# LDO.net
KiCad netlist of a schematic drawn in Altium Designer
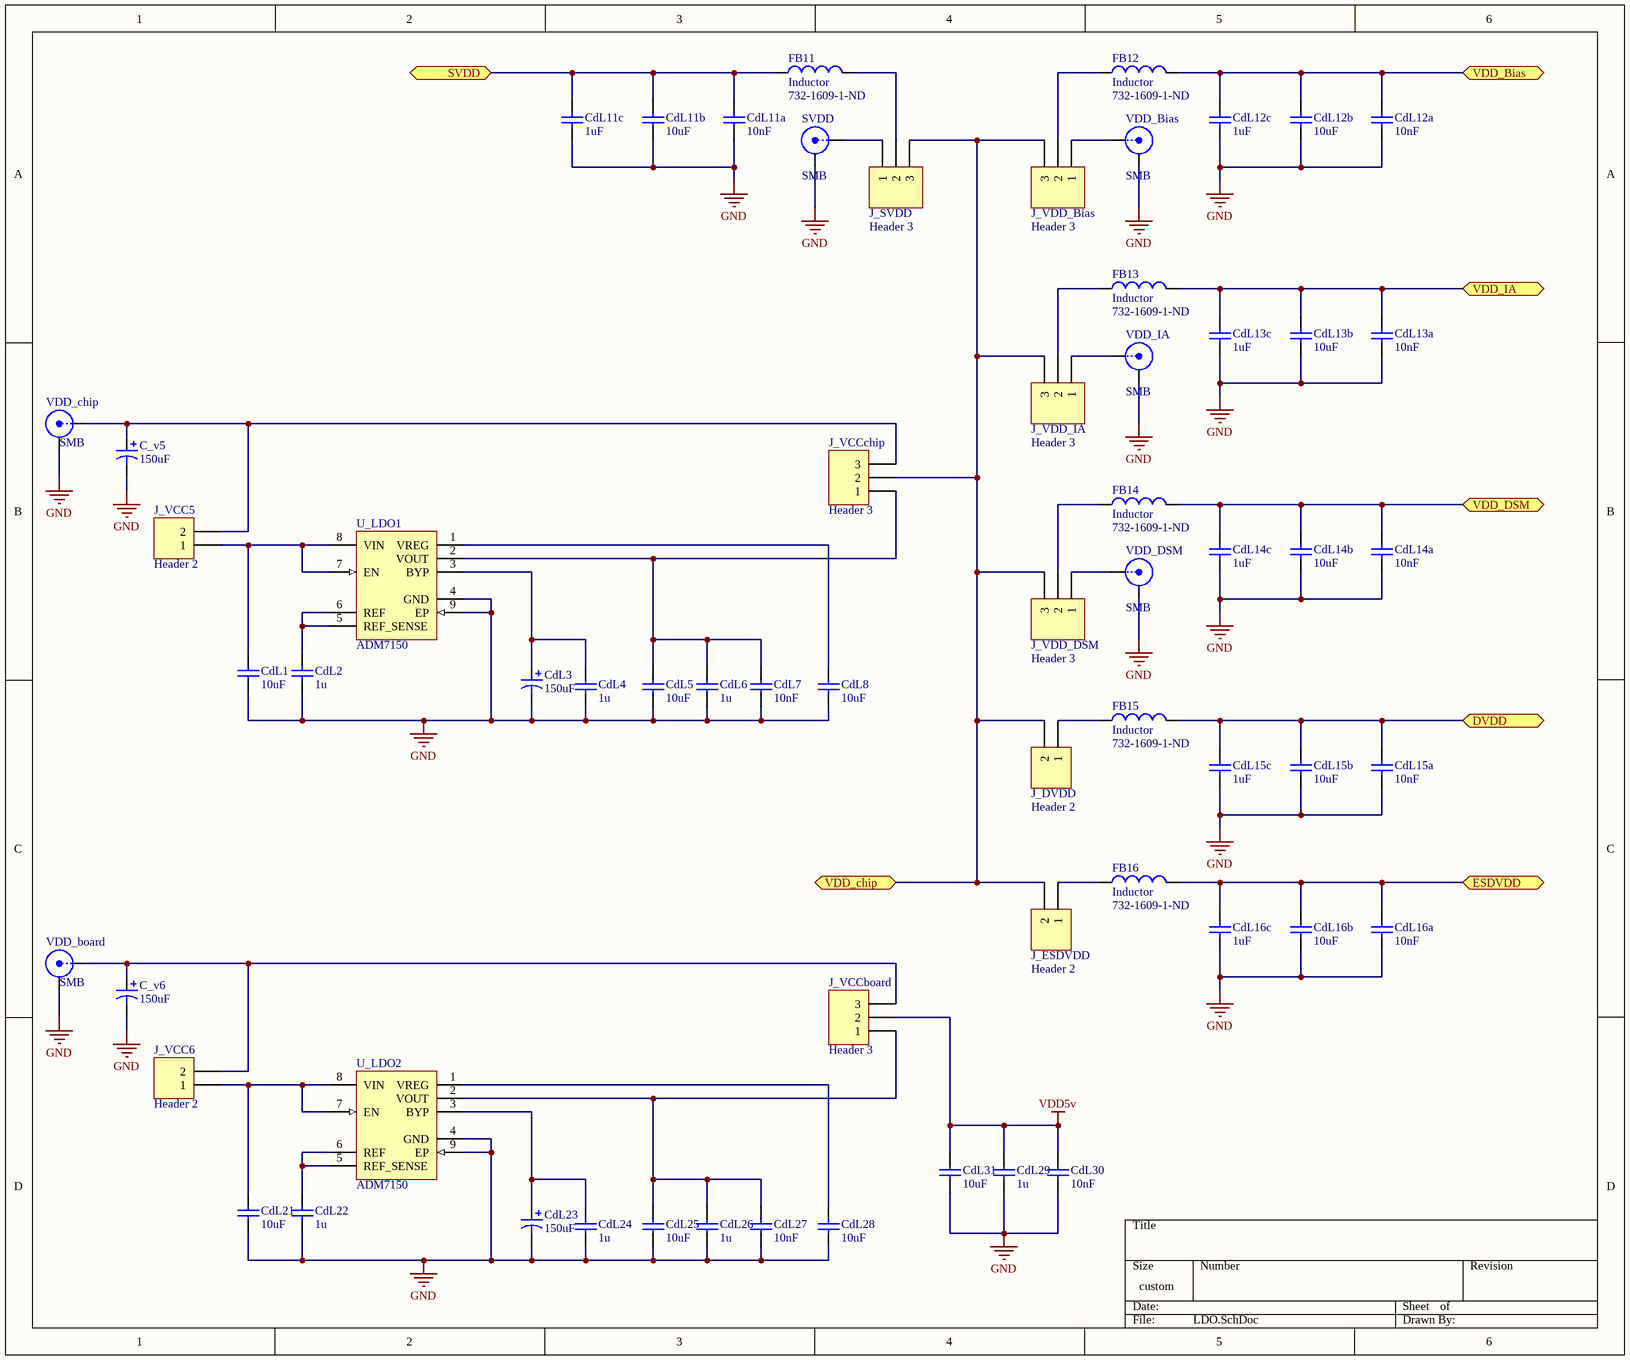
[diagram p0: LDO.SchDoc]

(export (version "E")
  (design (tool "Eeschema 10.0.6"))
  (components
    (comp (ref "CdL1")
      (value "10uF")
      (footprint "6-0805_M")
      (description "Capacitor")
      (fields (field (name "Comment") "Cap") (field (name "PUBLISHER") "Altium Limited"))
      (libsource (lib "Miscellaneous Devices") (part "Cap"))
    )
    (comp (ref "CdL2")
      (value "1u")
      (footprint "6-0805_M")
      (description "Capacitor")
      (fields (field (name "Comment") "Cap") (field (name "PUBLISHER") "Altium Limited"))
      (libsource (lib "Miscellaneous Devices") (part "Cap"))
    )
    (comp (ref "CdL3")
      (value "150uF")
      (footprint "C1210_M")
      (description "Polarized Capacitor (Radial)")
      (fields (field (name "Comment") "Cap Pol1") (field (name "PUBLISHER") "Altium Limited"))
      (libsource (lib "Miscellaneous Devices") (part "Cap Pol1"))
    )
    (comp (ref "CdL4")
      (value "1u")
      (footprint "6-0805_M")
      (description "Capacitor")
      (fields (field (name "Comment") "Cap") (field (name "PUBLISHER") "Altium Limited"))
      (libsource (lib "Miscellaneous Devices") (part "Cap"))
    )
    (comp (ref "CdL5")
      (value "10uF")
      (footprint "6-0805_M")
      (description "Capacitor")
      (fields (field (name "Comment") "Cap") (field (name "PUBLISHER") "Altium Limited"))
      (libsource (lib "Miscellaneous Devices") (part "Cap"))
    )
    (comp (ref "CdL6")
      (value "1u")
      (footprint "6-0805_M")
      (description "Capacitor")
      (fields (field (name "Comment") "Cap") (field (name "PUBLISHER") "Altium Limited"))
      (libsource (lib "Miscellaneous Devices") (part "Cap"))
    )
    (comp (ref "CdL7")
      (value "10nF")
      (footprint "6-0805_M")
      (description "Capacitor")
      (fields (field (name "Comment") "Cap") (field (name "PUBLISHER") "Altium Limited"))
      (libsource (lib "Miscellaneous Devices") (part "Cap"))
    )
    (comp (ref "CdL8")
      (value "10uF")
      (footprint "6-0805_M")
      (description "Capacitor")
      (fields (field (name "Comment") "Cap") (field (name "PUBLISHER") "Altium Limited"))
      (libsource (lib "Miscellaneous Devices") (part "Cap"))
    )
    (comp (ref "CdL11a")
      (value "10nF")
      (footprint "1608[0603]")
      (description "Capacitor")
      (fields (field (name "Comment") "Cap") (field (name "PUBLISHER") "Altium Limited"))
      (libsource (lib "Miscellaneous Devices") (part "Cap"))
    )
    (comp (ref "CdL11b")
      (value "10uF")
      (footprint "1608[0603]")
      (description "Capacitor")
      (fields (field (name "Comment") "Cap") (field (name "PUBLISHER") "Altium Limited"))
      (libsource (lib "Miscellaneous Devices") (part "Cap"))
    )
    (comp (ref "CdL11c")
      (value "1uF")
      (footprint "1608[0603]")
      (description "Capacitor")
      (fields (field (name "Comment") "Cap") (field (name "PUBLISHER") "Altium Limited"))
      (libsource (lib "Miscellaneous Devices") (part "Cap"))
    )
    (comp (ref "CdL12a")
      (value "10nF")
      (footprint "1608[0603]")
      (description "Capacitor")
      (fields (field (name "Comment") "Cap") (field (name "PUBLISHER") "Altium Limited"))
      (libsource (lib "Miscellaneous Devices") (part "Cap"))
    )
    (comp (ref "CdL12b")
      (value "10uF")
      (footprint "1608[0603]")
      (description "Capacitor")
      (fields (field (name "Comment") "Cap") (field (name "PUBLISHER") "Altium Limited"))
      (libsource (lib "Miscellaneous Devices") (part "Cap"))
    )
    (comp (ref "CdL12c")
      (value "1uF")
      (footprint "1608[0603]")
      (description "Capacitor")
      (fields (field (name "Comment") "Cap") (field (name "PUBLISHER") "Altium Limited"))
      (libsource (lib "Miscellaneous Devices") (part "Cap"))
    )
    (comp (ref "CdL13a")
      (value "10nF")
      (footprint "1608[0603]")
      (description "Capacitor")
      (fields (field (name "Comment") "Cap") (field (name "PUBLISHER") "Altium Limited"))
      (libsource (lib "Miscellaneous Devices") (part "Cap"))
    )
    (comp (ref "CdL13b")
      (value "10uF")
      (footprint "1608[0603]")
      (description "Capacitor")
      (fields (field (name "Comment") "Cap") (field (name "PUBLISHER") "Altium Limited"))
      (libsource (lib "Miscellaneous Devices") (part "Cap"))
    )
    (comp (ref "CdL13c")
      (value "1uF")
      (footprint "1608[0603]")
      (description "Capacitor")
      (fields (field (name "Comment") "Cap") (field (name "PUBLISHER") "Altium Limited"))
      (libsource (lib "Miscellaneous Devices") (part "Cap"))
    )
    (comp (ref "CdL14a")
      (value "10nF")
      (footprint "1608[0603]")
      (description "Capacitor")
      (fields (field (name "Comment") "Cap") (field (name "PUBLISHER") "Altium Limited"))
      (libsource (lib "Miscellaneous Devices") (part "Cap"))
    )
    (comp (ref "CdL14b")
      (value "10uF")
      (footprint "1608[0603]")
      (description "Capacitor")
      (fields (field (name "Comment") "Cap") (field (name "PUBLISHER") "Altium Limited"))
      (libsource (lib "Miscellaneous Devices") (part "Cap"))
    )
    (comp (ref "CdL14c")
      (value "1uF")
      (footprint "1608[0603]")
      (description "Capacitor")
      (fields (field (name "Comment") "Cap") (field (name "PUBLISHER") "Altium Limited"))
      (libsource (lib "Miscellaneous Devices") (part "Cap"))
    )
    (comp (ref "CdL15a")
      (value "10nF")
      (footprint "1608[0603]")
      (description "Capacitor")
      (fields (field (name "Comment") "Cap") (field (name "PUBLISHER") "Altium Limited"))
      (libsource (lib "Miscellaneous Devices") (part "Cap"))
    )
    (comp (ref "CdL15b")
      (value "10uF")
      (footprint "1608[0603]")
      (description "Capacitor")
      (fields (field (name "Comment") "Cap") (field (name "PUBLISHER") "Altium Limited"))
      (libsource (lib "Miscellaneous Devices") (part "Cap"))
    )
    (comp (ref "CdL15c")
      (value "1uF")
      (footprint "1608[0603]")
      (description "Capacitor")
      (fields (field (name "Comment") "Cap") (field (name "PUBLISHER") "Altium Limited"))
      (libsource (lib "Miscellaneous Devices") (part "Cap"))
    )
    (comp (ref "CdL16a")
      (value "10nF")
      (footprint "1608[0603]")
      (description "Capacitor")
      (fields (field (name "Comment") "Cap") (field (name "PUBLISHER") "Altium Limited"))
      (libsource (lib "Miscellaneous Devices") (part "Cap"))
    )
    (comp (ref "CdL16b")
      (value "10uF")
      (footprint "1608[0603]")
      (description "Capacitor")
      (fields (field (name "Comment") "Cap") (field (name "PUBLISHER") "Altium Limited"))
      (libsource (lib "Miscellaneous Devices") (part "Cap"))
    )
    (comp (ref "CdL16c")
      (value "1uF")
      (footprint "1608[0603]")
      (description "Capacitor")
      (fields (field (name "Comment") "Cap") (field (name "PUBLISHER") "Altium Limited"))
      (libsource (lib "Miscellaneous Devices") (part "Cap"))
    )
    (comp (ref "CdL21")
      (value "10uF")
      (footprint "6-0805_M")
      (description "Capacitor")
      (fields (field (name "Comment") "Cap") (field (name "PUBLISHER") "Altium Limited"))
      (libsource (lib "Miscellaneous Devices") (part "Cap"))
    )
    (comp (ref "CdL22")
      (value "1u")
      (footprint "6-0805_M")
      (description "Capacitor")
      (fields (field (name "Comment") "Cap") (field (name "PUBLISHER") "Altium Limited"))
      (libsource (lib "Miscellaneous Devices") (part "Cap"))
    )
    (comp (ref "CdL23")
      (value "150uF")
      (footprint "C1210_M")
      (description "Polarized Capacitor (Radial)")
      (fields (field (name "Comment") "Cap Pol1") (field (name "PUBLISHER") "Altium Limited"))
      (libsource (lib "Miscellaneous Devices") (part "Cap Pol1"))
    )
    (comp (ref "CdL24")
      (value "1u")
      (footprint "6-0805_M")
      (description "Capacitor")
      (fields (field (name "Comment") "Cap") (field (name "PUBLISHER") "Altium Limited"))
      (libsource (lib "Miscellaneous Devices") (part "Cap"))
    )
    (comp (ref "CdL25")
      (value "10uF")
      (footprint "6-0805_M")
      (description "Capacitor")
      (fields (field (name "Comment") "Cap") (field (name "PUBLISHER") "Altium Limited"))
      (libsource (lib "Miscellaneous Devices") (part "Cap"))
    )
    (comp (ref "CdL26")
      (value "1u")
      (footprint "6-0805_M")
      (description "Capacitor")
      (fields (field (name "Comment") "Cap") (field (name "PUBLISHER") "Altium Limited"))
      (libsource (lib "Miscellaneous Devices") (part "Cap"))
    )
    (comp (ref "CdL27")
      (value "10nF")
      (footprint "6-0805_M")
      (description "Capacitor")
      (fields (field (name "Comment") "Cap") (field (name "PUBLISHER") "Altium Limited"))
      (libsource (lib "Miscellaneous Devices") (part "Cap"))
    )
    (comp (ref "CdL28")
      (value "10uF")
      (footprint "6-0805_M")
      (description "Capacitor")
      (fields (field (name "Comment") "Cap") (field (name "PUBLISHER") "Altium Limited"))
      (libsource (lib "Miscellaneous Devices") (part "Cap"))
    )
    (comp (ref "CdL29")
      (value "1u")
      (footprint "6-0805_M")
      (description "Capacitor")
      (fields (field (name "Comment") "Cap") (field (name "PUBLISHER") "Altium Limited"))
      (libsource (lib "Miscellaneous Devices") (part "Cap"))
    )
    (comp (ref "CdL30")
      (value "10nF")
      (footprint "6-0805_M")
      (description "Capacitor")
      (fields (field (name "Comment") "Cap") (field (name "PUBLISHER") "Altium Limited"))
      (libsource (lib "Miscellaneous Devices") (part "Cap"))
    )
    (comp (ref "CdL31")
      (value "10uF")
      (footprint "6-0805_M")
      (description "Capacitor")
      (fields (field (name "Comment") "Cap") (field (name "PUBLISHER") "Altium Limited"))
      (libsource (lib "Miscellaneous Devices") (part "Cap"))
    )
    (comp (ref "C_v5")
      (value "150uF")
      (footprint "C1210_M")
      (description "Polarized Capacitor (Radial)")
      (fields (field (name "Comment") "Cap Pol1") (field (name "PUBLISHER") "Altium Limited"))
      (libsource (lib "Miscellaneous Devices") (part "Cap Pol1"))
    )
    (comp (ref "C_v6")
      (value "150uF")
      (footprint "C1210_M")
      (description "Polarized Capacitor (Radial)")
      (fields (field (name "Comment") "Cap Pol1") (field (name "PUBLISHER") "Altium Limited"))
      (libsource (lib "Miscellaneous Devices") (part "Cap Pol1"))
    )
    (comp (ref "FB11")
      (value "Inductor")
      (footprint "C0805")
      (fields
        (field (name "SUPPLIER PART NUMBER 1") "732-1609-1-ND")
        (field (name "MANUFACTURER") "Wurth Electronics Inc")
        (field (name "MANUFACTURER PART NUMBER") "742792093")
        (field (name "PUBLISHER") "Altium Limited")
      )
      (libsource (lib "") (part "Inductor_1"))
    )
    (comp (ref "FB12")
      (value "Inductor")
      (footprint "C0805")
      (fields
        (field (name "SUPPLIER PART NUMBER 1") "732-1609-1-ND")
        (field (name "MANUFACTURER") "Wurth Electronics Inc")
        (field (name "MANUFACTURER PART NUMBER") "742792093")
        (field (name "PUBLISHER") "Altium Limited")
      )
      (libsource (lib "Miscellaneous Devices") (part "Inductor"))
    )
    (comp (ref "FB13")
      (value "Inductor")
      (footprint "C0805")
      (fields
        (field (name "SUPPLIER PART NUMBER 1") "732-1609-1-ND")
        (field (name "MANUFACTURER") "Wurth Electronics Inc")
        (field (name "MANUFACTURER PART NUMBER") "742792093")
        (field (name "PUBLISHER") "Altium Limited")
      )
      (libsource (lib "Miscellaneous Devices") (part "Inductor"))
    )
    (comp (ref "FB14")
      (value "Inductor")
      (footprint "C0805")
      (fields
        (field (name "SUPPLIER PART NUMBER 1") "732-1609-1-ND")
        (field (name "MANUFACTURER") "Wurth Electronics Inc")
        (field (name "MANUFACTURER PART NUMBER") "742792093")
        (field (name "PUBLISHER") "Altium Limited")
      )
      (libsource (lib "Miscellaneous Devices") (part "Inductor"))
    )
    (comp (ref "FB15")
      (value "Inductor")
      (footprint "C0805")
      (fields
        (field (name "SUPPLIER PART NUMBER 1") "732-1609-1-ND")
        (field (name "MANUFACTURER") "Wurth Electronics Inc")
        (field (name "MANUFACTURER PART NUMBER") "742792093")
        (field (name "PUBLISHER") "Altium Limited")
      )
      (libsource (lib "Miscellaneous Devices") (part "Inductor"))
    )
    (comp (ref "FB16")
      (value "Inductor")
      (footprint "C0805")
      (fields
        (field (name "SUPPLIER PART NUMBER 1") "732-1609-1-ND")
        (field (name "MANUFACTURER") "Wurth Electronics Inc")
        (field (name "MANUFACTURER PART NUMBER") "742792093")
        (field (name "PUBLISHER") "Altium Limited")
      )
      (libsource (lib "Miscellaneous Devices") (part "Inductor"))
    )
    (comp (ref "J_DVDD")
      (value "Header 2")
      (footprint "HDR1X2")
      (description "Header, 2-Pin")
      (fields (field (name "PUBLISHER") "Altium Limited"))
      (libsource (lib "") (part "Header 2_1"))
    )
    (comp (ref "J_ESDVDD")
      (value "Header 2")
      (footprint "HDR1X2")
      (description "Header, 2-Pin")
      (fields (field (name "PUBLISHER") "Altium Limited"))
      (libsource (lib "") (part "Header 2_1"))
    )
    (comp (ref "J_SVDD")
      (value "Header 3")
      (footprint "HDR1X3")
      (description "Header, 3-Pin")
      (fields (field (name "PUBLISHER") "Altium Limited"))
      (libsource (lib "Miscellaneous Connectors") (part "Header 3"))
    )
    (comp (ref "J_VCC5")
      (value "Header 2")
      (footprint "HDR1X2")
      (description "Header, 2-Pin")
      (fields (field (name "PUBLISHER") "Altium Limited"))
      (libsource (lib "Miscellaneous Connectors") (part "Header 2"))
    )
    (comp (ref "J_VCC6")
      (value "Header 2")
      (footprint "HDR1X2")
      (description "Header, 2-Pin")
      (fields (field (name "PUBLISHER") "Altium Limited"))
      (libsource (lib "Miscellaneous Connectors") (part "Header 2"))
    )
    (comp (ref "J_VCCboard")
      (value "Header 3")
      (footprint "HDR1X3")
      (description "Header, 3-Pin")
      (fields (field (name "PUBLISHER") "Altium Limited"))
      (libsource (lib "Miscellaneous Connectors") (part "Header 3"))
    )
    (comp (ref "J_VCCchip")
      (value "Header 3")
      (footprint "HDR1X3")
      (description "Header, 3-Pin")
      (fields (field (name "PUBLISHER") "Altium Limited"))
      (libsource (lib "Miscellaneous Connectors") (part "Header 3"))
    )
    (comp (ref "J_VDD_Bias")
      (value "Header 3")
      (footprint "HDR1X3")
      (description "Header, 3-Pin")
      (fields (field (name "PUBLISHER") "Altium Limited"))
      (libsource (lib "") (part "Header 3_1"))
    )
    (comp (ref "J_VDD_DSM")
      (value "Header 3")
      (footprint "HDR1X3")
      (description "Header, 3-Pin")
      (fields (field (name "PUBLISHER") "Altium Limited"))
      (libsource (lib "") (part "Header 3_1"))
    )
    (comp (ref "J_VDD_IA")
      (value "Header 3")
      (footprint "HDR1X3")
      (description "Header, 3-Pin")
      (fields (field (name "PUBLISHER") "Altium Limited"))
      (libsource (lib "") (part "Header 3_1"))
    )
    (comp (ref "SVDD")
      (value "SMB")
      (footprint "SMB_V-RJ45")
      (description "SMB Straight Connector")
      (fields (field (name "PUBLISHER") "Altium Limited"))
      (libsource (lib "Miscellaneous Connectors") (part "SMB"))
    )
    (comp (ref "U_LDO1")
      (value "ADM7150")
      (footprint "ADM7150")
      (description "800 mA Ultralow Noise, High PSRR, RF Linear Regulator")
      (fields (field (name "MANUFACTURER") "Analog Devices") (field (name "PARTNUMBER") "ADP1707ARDZ-3.3-R7"))
      (libsource (lib "custom") (part "ADM7150"))
    )
    (comp (ref "U_LDO2")
      (value "ADM7150")
      (footprint "ADM7150")
      (description "800 mA Ultralow Noise, High PSRR, RF Linear Regulator")
      (fields (field (name "MANUFACTURER") "Analog Devices") (field (name "PARTNUMBER") "ADP1707ARDZ-3.3-R7"))
      (libsource (lib "custom") (part "ADM7150"))
    )
    (comp (ref "VDD_Bias")
      (value "SMB")
      (footprint "SMB_V-RJ45")
      (description "SMB Straight Connector")
      (fields (field (name "PUBLISHER") "Altium Limited"))
      (libsource (lib "Miscellaneous Connectors") (part "SMB"))
    )
    (comp (ref "VDD_board")
      (value "SMB")
      (footprint "SMB_V-RJ45")
      (description "SMB Straight Connector")
      (fields (field (name "PUBLISHER") "Altium Limited"))
      (libsource (lib "Miscellaneous Connectors") (part "SMB"))
    )
    (comp (ref "VDD_chip")
      (value "SMB")
      (footprint "SMB_V-RJ45")
      (description "SMB Straight Connector")
      (fields (field (name "PUBLISHER") "Altium Limited"))
      (libsource (lib "Miscellaneous Connectors") (part "SMB"))
    )
    (comp (ref "VDD_DSM")
      (value "SMB")
      (footprint "SMB_V-RJ45")
      (description "SMB Straight Connector")
      (fields (field (name "PUBLISHER") "Altium Limited"))
      (libsource (lib "Miscellaneous Connectors") (part "SMB"))
    )
    (comp (ref "VDD_IA")
      (value "SMB")
      (footprint "SMB_V-RJ45")
      (description "SMB Straight Connector")
      (fields (field (name "PUBLISHER") "Altium Limited"))
      (libsource (lib "Miscellaneous Connectors") (part "SMB"))
    )
  )
  (nets
    (net (code "1") (name "/DVDD") (class "Default")
      (node (ref "CdL15a") (pin "1") (pinfunction "1_1") (pintype "passive"))
      (node (ref "CdL15b") (pin "1") (pinfunction "1_1") (pintype "passive"))
      (node (ref "CdL15c") (pin "1") (pinfunction "1_1") (pintype "passive"))
      (node (ref "FB15") (pin "2") (pinfunction "2_2") (pintype "passive"))
    )
    (net (code "2") (name "/ESDVDD") (class "Default")
      (node (ref "CdL16a") (pin "1") (pinfunction "1_1") (pintype "passive"))
      (node (ref "CdL16b") (pin "1") (pinfunction "1_1") (pintype "passive"))
      (node (ref "CdL16c") (pin "1") (pinfunction "1_1") (pintype "passive"))
      (node (ref "FB16") (pin "2") (pinfunction "2_2") (pintype "passive"))
    )
    (net (code "3") (name "/SVDD") (class "Default")
      (node (ref "CdL11a") (pin "1") (pinfunction "1_1") (pintype "passive"))
      (node (ref "CdL11b") (pin "1") (pinfunction "1_1") (pintype "passive"))
      (node (ref "CdL11c") (pin "1") (pinfunction "1_1") (pintype "passive"))
      (node (ref "FB11") (pin "2") (pinfunction "2_2") (pintype "passive"))
    )
    (net (code "4") (name "/VDD_Bias") (class "Default")
      (node (ref "CdL12a") (pin "1") (pinfunction "1_1") (pintype "passive"))
      (node (ref "CdL12b") (pin "1") (pinfunction "1_1") (pintype "passive"))
      (node (ref "CdL12c") (pin "1") (pinfunction "1_1") (pintype "passive"))
      (node (ref "FB12") (pin "2") (pinfunction "2_2") (pintype "passive"))
    )
    (net (code "5") (name "/VDD_DSM") (class "Default")
      (node (ref "CdL14a") (pin "1") (pinfunction "1_1") (pintype "passive"))
      (node (ref "CdL14b") (pin "1") (pinfunction "1_1") (pintype "passive"))
      (node (ref "CdL14c") (pin "1") (pinfunction "1_1") (pintype "passive"))
      (node (ref "FB14") (pin "2") (pinfunction "2_2") (pintype "passive"))
    )
    (net (code "6") (name "/VDD_IA") (class "Default")
      (node (ref "CdL13a") (pin "1") (pinfunction "1_1") (pintype "passive"))
      (node (ref "CdL13b") (pin "1") (pinfunction "1_1") (pintype "passive"))
      (node (ref "CdL13c") (pin "1") (pinfunction "1_1") (pintype "passive"))
      (node (ref "FB13") (pin "2") (pinfunction "2_2") (pintype "passive"))
    )
    (net (code "7") (name "/VDD_chip") (class "Default")
      (node (ref "J_DVDD") (pin "2") (pinfunction "2_2") (pintype "passive"))
      (node (ref "J_ESDVDD") (pin "2") (pinfunction "2_2") (pintype "passive"))
      (node (ref "J_SVDD") (pin "3") (pinfunction "3_3") (pintype "passive"))
      (node (ref "J_VCCchip") (pin "2") (pinfunction "2_2") (pintype "passive"))
      (node (ref "J_VDD_Bias") (pin "3") (pinfunction "3_3") (pintype "passive"))
      (node (ref "J_VDD_DSM") (pin "3") (pinfunction "3_3") (pintype "passive"))
      (node (ref "J_VDD_IA") (pin "3") (pinfunction "3_3") (pintype "passive"))
    )
    (net (code "8") (name "GND") (class "Default")
      (node (ref "C_v5") (pin "2") (pinfunction "2_2") (pintype "passive"))
      (node (ref "C_v6") (pin "2") (pinfunction "2_2") (pintype "passive"))
      (node (ref "CdL1") (pin "1") (pinfunction "1_1") (pintype "passive"))
      (node (ref "CdL11a") (pin "2") (pinfunction "2_2") (pintype "passive"))
      (node (ref "CdL11b") (pin "2") (pinfunction "2_2") (pintype "passive"))
      (node (ref "CdL11c") (pin "2") (pinfunction "2_2") (pintype "passive"))
      (node (ref "CdL12a") (pin "2") (pinfunction "2_2") (pintype "passive"))
      (node (ref "CdL12b") (pin "2") (pinfunction "2_2") (pintype "passive"))
      (node (ref "CdL12c") (pin "2") (pinfunction "2_2") (pintype "passive"))
      (node (ref "CdL13a") (pin "2") (pinfunction "2_2") (pintype "passive"))
      (node (ref "CdL13b") (pin "2") (pinfunction "2_2") (pintype "passive"))
      (node (ref "CdL13c") (pin "2") (pinfunction "2_2") (pintype "passive"))
      (node (ref "CdL14a") (pin "2") (pinfunction "2_2") (pintype "passive"))
      (node (ref "CdL14b") (pin "2") (pinfunction "2_2") (pintype "passive"))
      (node (ref "CdL14c") (pin "2") (pinfunction "2_2") (pintype "passive"))
      (node (ref "CdL15a") (pin "2") (pinfunction "2_2") (pintype "passive"))
      (node (ref "CdL15b") (pin "2") (pinfunction "2_2") (pintype "passive"))
      (node (ref "CdL15c") (pin "2") (pinfunction "2_2") (pintype "passive"))
      (node (ref "CdL16a") (pin "2") (pinfunction "2_2") (pintype "passive"))
      (node (ref "CdL16b") (pin "2") (pinfunction "2_2") (pintype "passive"))
      (node (ref "CdL16c") (pin "2") (pinfunction "2_2") (pintype "passive"))
      (node (ref "CdL2") (pin "1") (pinfunction "1_1") (pintype "passive"))
      (node (ref "CdL21") (pin "1") (pinfunction "1_1") (pintype "passive"))
      (node (ref "CdL22") (pin "1") (pinfunction "1_1") (pintype "passive"))
      (node (ref "CdL23") (pin "2") (pinfunction "2_2") (pintype "passive"))
      (node (ref "CdL24") (pin "1") (pinfunction "1_1") (pintype "passive"))
      (node (ref "CdL25") (pin "1") (pinfunction "1_1") (pintype "passive"))
      (node (ref "CdL26") (pin "1") (pinfunction "1_1") (pintype "passive"))
      (node (ref "CdL27") (pin "1") (pinfunction "1_1") (pintype "passive"))
      (node (ref "CdL28") (pin "2") (pinfunction "2_2") (pintype "passive"))
      (node (ref "CdL29") (pin "1") (pinfunction "1_1") (pintype "passive"))
      (node (ref "CdL3") (pin "2") (pinfunction "2_2") (pintype "passive"))
      (node (ref "CdL30") (pin "1") (pinfunction "1_1") (pintype "passive"))
      (node (ref "CdL31") (pin "1") (pinfunction "1_1") (pintype "passive"))
      (node (ref "CdL4") (pin "1") (pinfunction "1_1") (pintype "passive"))
      (node (ref "CdL5") (pin "1") (pinfunction "1_1") (pintype "passive"))
      (node (ref "CdL6") (pin "1") (pinfunction "1_1") (pintype "passive"))
      (node (ref "CdL7") (pin "1") (pinfunction "1_1") (pintype "passive"))
      (node (ref "CdL8") (pin "2") (pinfunction "2_2") (pintype "passive"))
      (node (ref "SVDD") (pin "2") (pinfunction "Y_2") (pintype "passive"))
      (node (ref "U_LDO1") (pin "4") (pinfunction "GND_4") (pintype "passive"))
      (node (ref "U_LDO1") (pin "9") (pinfunction "EP_9") (pintype "input"))
      (node (ref "U_LDO2") (pin "4") (pinfunction "GND_4") (pintype "passive"))
      (node (ref "U_LDO2") (pin "9") (pinfunction "EP_9") (pintype "input"))
      (node (ref "VDD_Bias") (pin "2") (pinfunction "Y_2") (pintype "passive"))
      (node (ref "VDD_DSM") (pin "2") (pinfunction "Y_2") (pintype "passive"))
      (node (ref "VDD_IA") (pin "2") (pinfunction "Y_2") (pintype "passive"))
      (node (ref "VDD_board") (pin "2") (pinfunction "Y_2") (pintype "passive"))
      (node (ref "VDD_chip") (pin "2") (pinfunction "Y_2") (pintype "passive"))
    )
    (net (code "9") (name "Net-(FB11-Pad1)") (class "Default")
      (node (ref "FB11") (pin "1") (pinfunction "1_1") (pintype "passive"))
      (node (ref "J_SVDD") (pin "2") (pinfunction "2_2") (pintype "passive"))
    )
    (net (code "10") (name "Net-(FB12-Pad1)") (class "Default")
      (node (ref "FB12") (pin "1") (pinfunction "1_1") (pintype "passive"))
      (node (ref "J_VDD_Bias") (pin "2") (pinfunction "2_2") (pintype "passive"))
    )
    (net (code "11") (name "Net-(FB13-Pad1)") (class "Default")
      (node (ref "FB13") (pin "1") (pinfunction "1_1") (pintype "passive"))
      (node (ref "J_VDD_IA") (pin "2") (pinfunction "2_2") (pintype "passive"))
    )
    (net (code "12") (name "Net-(FB14-Pad1)") (class "Default")
      (node (ref "FB14") (pin "1") (pinfunction "1_1") (pintype "passive"))
      (node (ref "J_VDD_DSM") (pin "2") (pinfunction "2_2") (pintype "passive"))
    )
    (net (code "13") (name "Net-(FB15-Pad1)") (class "Default")
      (node (ref "FB15") (pin "1") (pinfunction "1_1") (pintype "passive"))
      (node (ref "J_DVDD") (pin "1") (pinfunction "1_1") (pintype "passive"))
    )
    (net (code "14") (name "Net-(FB16-Pad1)") (class "Default")
      (node (ref "FB16") (pin "1") (pinfunction "1_1") (pintype "passive"))
      (node (ref "J_ESDVDD") (pin "1") (pinfunction "1_1") (pintype "passive"))
    )
    (net (code "15") (name "Net-(SVDD-X)") (class "Default")
      (node (ref "J_SVDD") (pin "1") (pinfunction "1_1") (pintype "passive"))
      (node (ref "SVDD") (pin "1") (pinfunction "X_1") (pintype "passive"))
    )
    (net (code "16") (name "Net-(U_LDO1-BYP)") (class "Default")
      (node (ref "CdL3") (pin "1") (pinfunction "1_1") (pintype "passive"))
      (node (ref "CdL4") (pin "2") (pinfunction "2_2") (pintype "passive"))
      (node (ref "U_LDO1") (pin "3") (pinfunction "BYP_3") (pintype "passive"))
    )
    (net (code "17") (name "Net-(U_LDO1-EN)") (class "Default")
      (node (ref "CdL1") (pin "2") (pinfunction "2_2") (pintype "passive"))
      (node (ref "J_VCC5") (pin "1") (pinfunction "1_1") (pintype "passive"))
      (node (ref "U_LDO1") (pin "7") (pinfunction "EN_7") (pintype "input"))
      (node (ref "U_LDO1") (pin "8") (pinfunction "VIN_8") (pintype "passive"))
    )
    (net (code "18") (name "Net-(U_LDO1-REF)") (class "Default")
      (node (ref "CdL2") (pin "2") (pinfunction "2_2") (pintype "passive"))
      (node (ref "U_LDO1") (pin "5") (pinfunction "REF_SENSE_5") (pintype "passive"))
      (node (ref "U_LDO1") (pin "6") (pinfunction "REF_6") (pintype "passive"))
    )
    (net (code "19") (name "Net-(U_LDO1-VOUT)") (class "Default")
      (node (ref "CdL5") (pin "2") (pinfunction "2_2") (pintype "passive"))
      (node (ref "CdL6") (pin "2") (pinfunction "2_2") (pintype "passive"))
      (node (ref "CdL7") (pin "2") (pinfunction "2_2") (pintype "passive"))
      (node (ref "J_VCCchip") (pin "1") (pinfunction "1_1") (pintype "passive"))
      (node (ref "U_LDO1") (pin "2") (pinfunction "VOUT_2") (pintype "passive"))
    )
    (net (code "20") (name "Net-(U_LDO1-VREG)") (class "Default")
      (node (ref "CdL8") (pin "1") (pinfunction "1_1") (pintype "passive"))
      (node (ref "U_LDO1") (pin "1") (pinfunction "VREG_1") (pintype "passive"))
    )
    (net (code "21") (name "Net-(U_LDO2-BYP)") (class "Default")
      (node (ref "CdL23") (pin "1") (pinfunction "1_1") (pintype "passive"))
      (node (ref "CdL24") (pin "2") (pinfunction "2_2") (pintype "passive"))
      (node (ref "U_LDO2") (pin "3") (pinfunction "BYP_3") (pintype "passive"))
    )
    (net (code "22") (name "Net-(U_LDO2-EN)") (class "Default")
      (node (ref "CdL21") (pin "2") (pinfunction "2_2") (pintype "passive"))
      (node (ref "J_VCC6") (pin "1") (pinfunction "1_1") (pintype "passive"))
      (node (ref "U_LDO2") (pin "7") (pinfunction "EN_7") (pintype "input"))
      (node (ref "U_LDO2") (pin "8") (pinfunction "VIN_8") (pintype "passive"))
    )
    (net (code "23") (name "Net-(U_LDO2-REF)") (class "Default")
      (node (ref "CdL22") (pin "2") (pinfunction "2_2") (pintype "passive"))
      (node (ref "U_LDO2") (pin "5") (pinfunction "REF_SENSE_5") (pintype "passive"))
      (node (ref "U_LDO2") (pin "6") (pinfunction "REF_6") (pintype "passive"))
    )
    (net (code "24") (name "Net-(U_LDO2-VOUT)") (class "Default")
      (node (ref "CdL25") (pin "2") (pinfunction "2_2") (pintype "passive"))
      (node (ref "CdL26") (pin "2") (pinfunction "2_2") (pintype "passive"))
      (node (ref "CdL27") (pin "2") (pinfunction "2_2") (pintype "passive"))
      (node (ref "J_VCCboard") (pin "1") (pinfunction "1_1") (pintype "passive"))
      (node (ref "U_LDO2") (pin "2") (pinfunction "VOUT_2") (pintype "passive"))
    )
    (net (code "25") (name "Net-(U_LDO2-VREG)") (class "Default")
      (node (ref "CdL28") (pin "1") (pinfunction "1_1") (pintype "passive"))
      (node (ref "U_LDO2") (pin "1") (pinfunction "VREG_1") (pintype "passive"))
    )
    (net (code "26") (name "Net-(VDD_Bias-X)") (class "Default")
      (node (ref "J_VDD_Bias") (pin "1") (pinfunction "1_1") (pintype "passive"))
      (node (ref "VDD_Bias") (pin "1") (pinfunction "X_1") (pintype "passive"))
    )
    (net (code "27") (name "Net-(VDD_DSM-X)") (class "Default")
      (node (ref "J_VDD_DSM") (pin "1") (pinfunction "1_1") (pintype "passive"))
      (node (ref "VDD_DSM") (pin "1") (pinfunction "X_1") (pintype "passive"))
    )
    (net (code "28") (name "Net-(VDD_IA-X)") (class "Default")
      (node (ref "J_VDD_IA") (pin "1") (pinfunction "1_1") (pintype "passive"))
      (node (ref "VDD_IA") (pin "1") (pinfunction "X_1") (pintype "passive"))
    )
    (net (code "29") (name "Net-(VDD_board-X)") (class "Default")
      (node (ref "C_v6") (pin "1") (pinfunction "1_1") (pintype "passive"))
      (node (ref "J_VCC6") (pin "2") (pinfunction "2_2") (pintype "passive"))
      (node (ref "J_VCCboard") (pin "3") (pinfunction "3_3") (pintype "passive"))
      (node (ref "VDD_board") (pin "1") (pinfunction "X_1") (pintype "passive"))
    )
    (net (code "30") (name "Net-(VDD_chip-X)") (class "Default")
      (node (ref "C_v5") (pin "1") (pinfunction "1_1") (pintype "passive"))
      (node (ref "J_VCC5") (pin "2") (pinfunction "2_2") (pintype "passive"))
      (node (ref "J_VCCchip") (pin "3") (pinfunction "3_3") (pintype "passive"))
      (node (ref "VDD_chip") (pin "1") (pinfunction "X_1") (pintype "passive"))
    )
    (net (code "31") (name "VDD5v") (class "Default")
      (node (ref "CdL29") (pin "2") (pinfunction "2_2") (pintype "passive"))
      (node (ref "CdL30") (pin "2") (pinfunction "2_2") (pintype "passive"))
      (node (ref "CdL31") (pin "2") (pinfunction "2_2") (pintype "passive"))
      (node (ref "J_VCCboard") (pin "2") (pinfunction "2_2") (pintype "passive"))
    )
  )
)
